# Mikrolysreklamen.net
KiCad netlist of a schematic drawn in Altium Designer
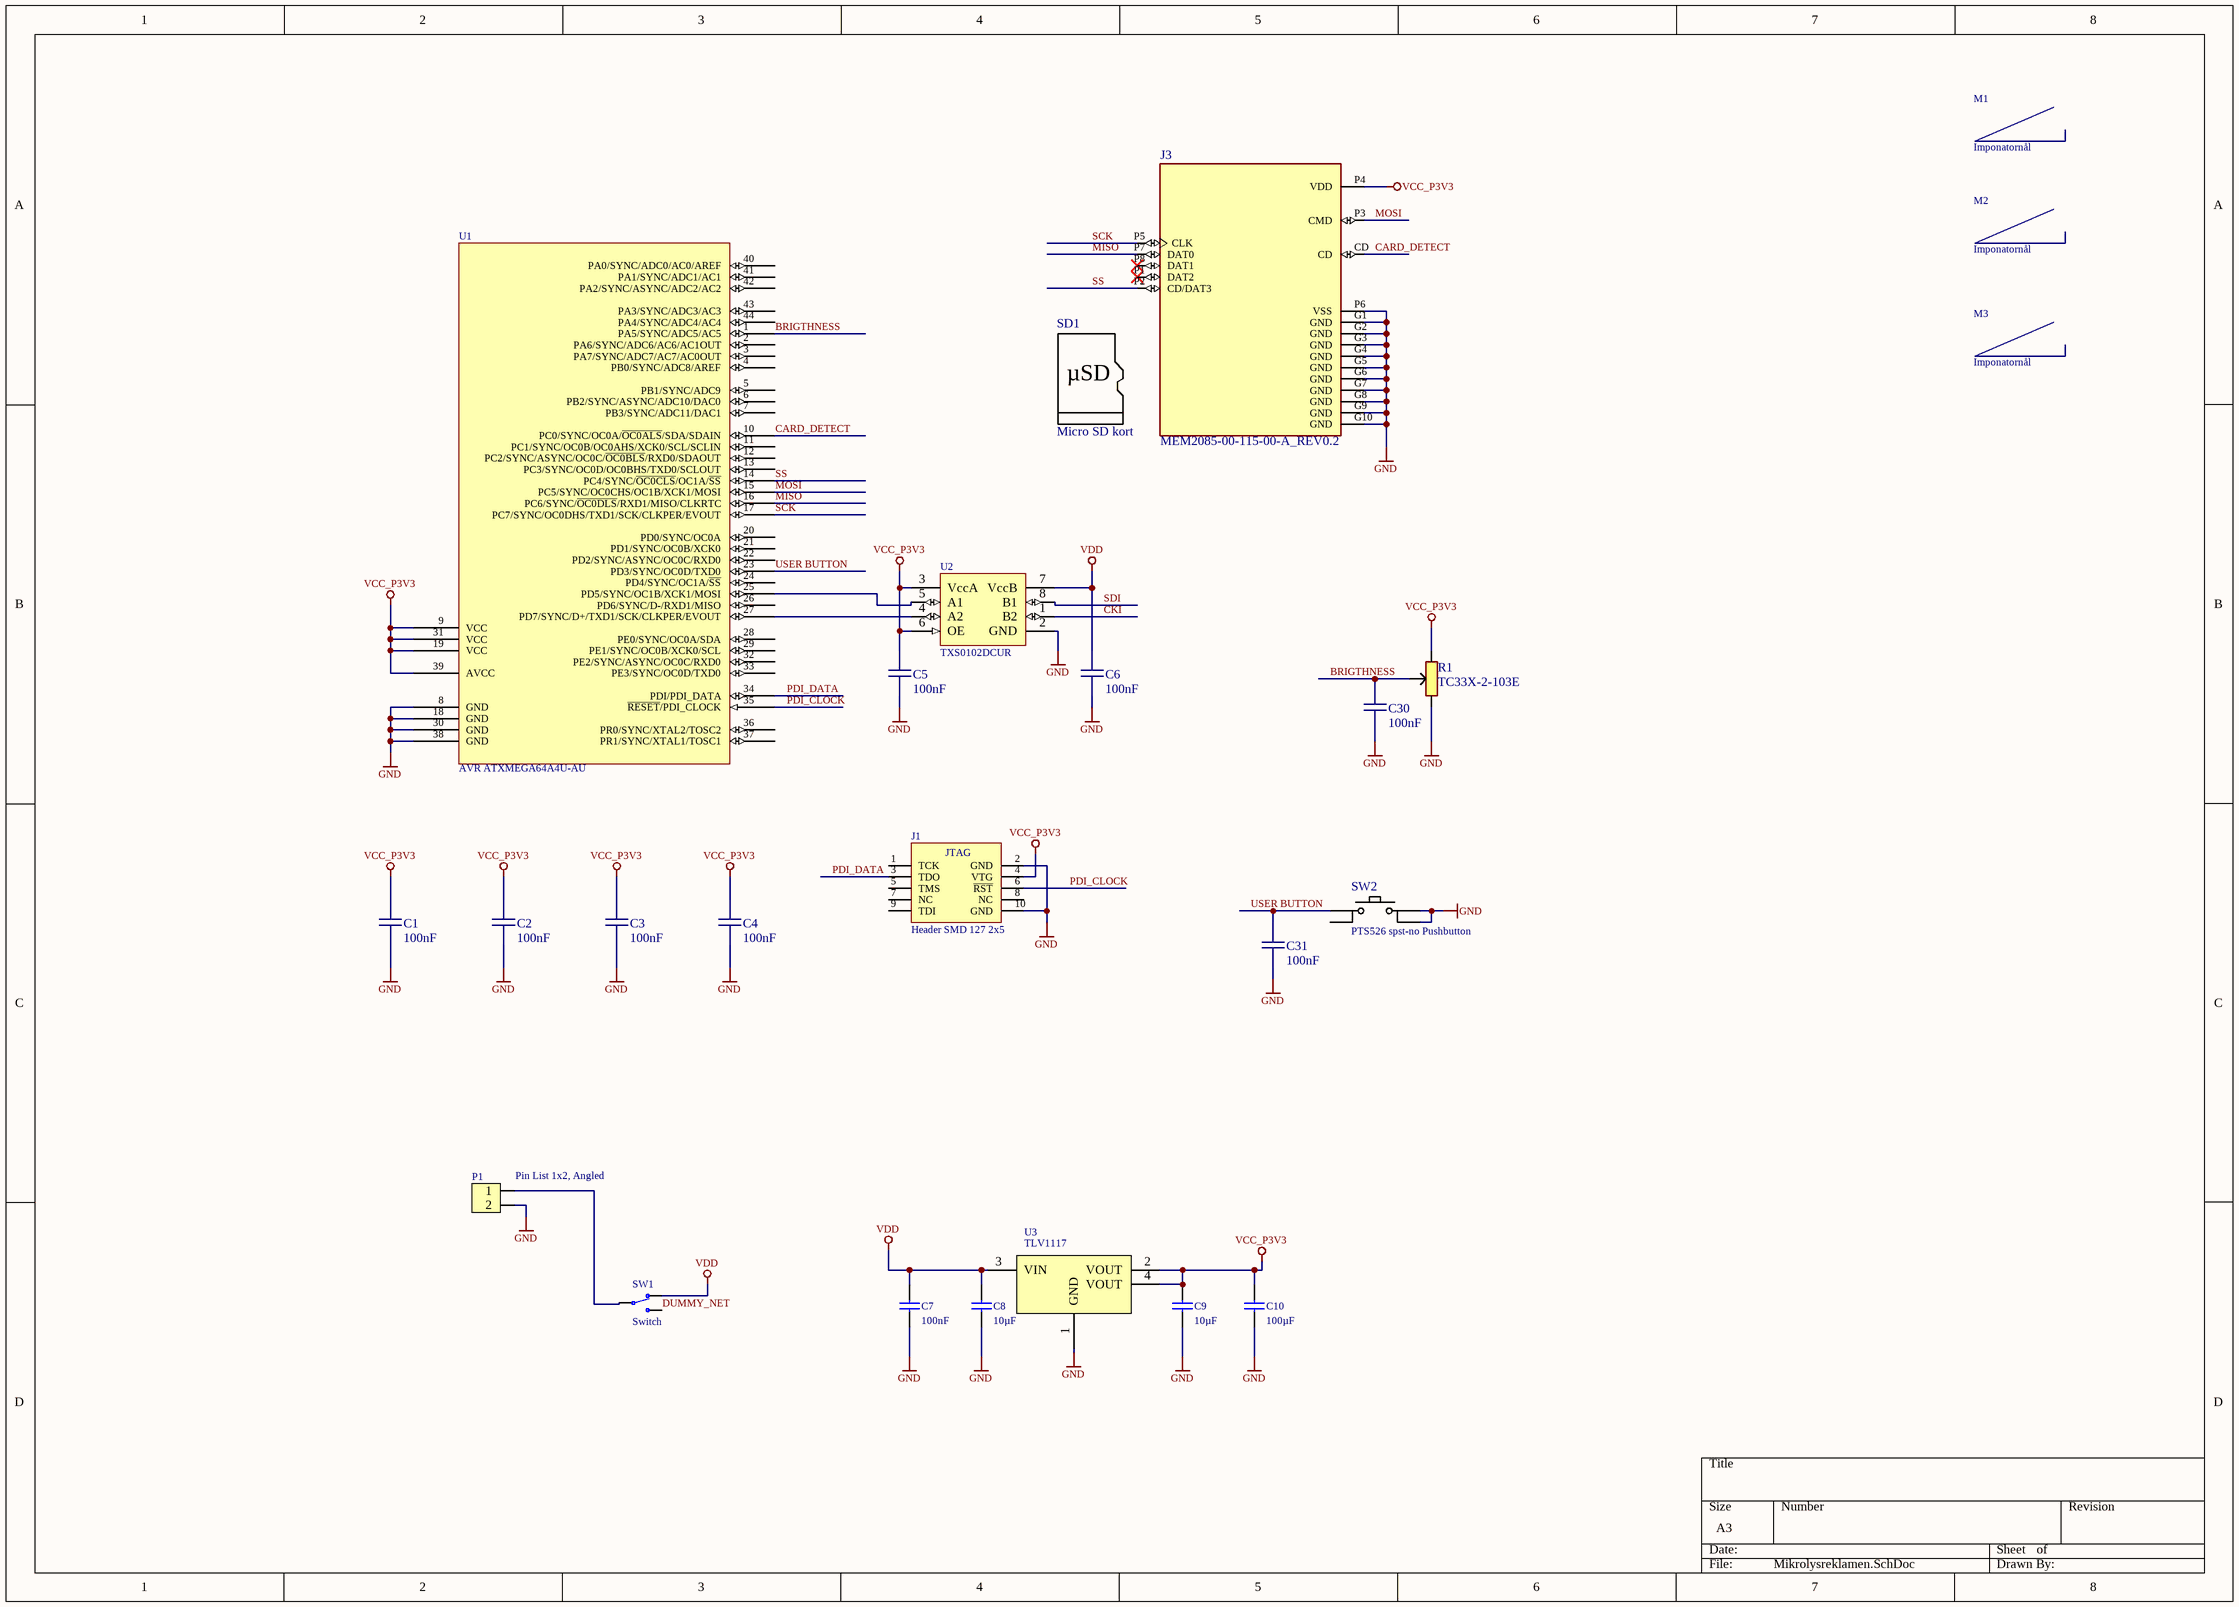
[diagram p0: Mikrolysreklamen.SchDoc]

(export (version "E")
  (design (tool "Eeschema 10.0.6"))
  (components
    (comp (ref "C1")
      (value "100nF")
      (footprint "CAPC0603(1608)55_N")
      (libsource (lib "OVLib_64") (part "CAP"))
    )
    (comp (ref "C2")
      (value "100nF")
      (footprint "CAPC0603(1608)55_N")
      (libsource (lib "OVLib_64") (part "CAP"))
    )
    (comp (ref "C3")
      (value "100nF")
      (footprint "CAPC0603(1608)55_N")
      (libsource (lib "OVLib_64") (part "CAP"))
    )
    (comp (ref "C4")
      (value "100nF")
      (footprint "CAPC0603(1608)55_N")
      (libsource (lib "OVLib_64") (part "CAP"))
    )
    (comp (ref "C5")
      (value "100nF")
      (footprint "CAPC0603(1608)55_N")
      (libsource (lib "OVLib_64") (part "CAP"))
    )
    (comp (ref "C6")
      (value "100nF")
      (footprint "CAPC0603(1608)55_N")
      (libsource (lib "OVLib_64") (part "CAP"))
    )
    (comp (ref "C7")
      (value "100nF")
      (footprint "CAPC1005X04L")
      (description "Capacitor, X7R, ±10%")
      (fields (field (name "PART NUMBER") "C0402-100n") (field (name "PUBLISHER") "Nordic Semiconductor"))
      (libsource (lib "Nordic Passive DB") (part "CAP"))
    )
    (comp (ref "C8")
      (value "10µF")
      (footprint "CAPC1608X06L")
      (description "Capacitor, X5R, ±20%")
      (fields (field (name "PART NUMBER") "C0603-10µ") (field (name "PUBLISHER") "Nordic Semiconductor"))
      (libsource (lib "Nordic Passive DB") (part "CAP"))
    )
    (comp (ref "C9")
      (value "10µF")
      (footprint "CAPC1608X06L")
      (description "Capacitor, X5R, ±20%")
      (fields (field (name "PART NUMBER") "C0603-10µ") (field (name "PUBLISHER") "Nordic Semiconductor"))
      (libsource (lib "Nordic Passive DB") (part "CAP"))
    )
    (comp (ref "C10")
      (value "100µF")
      (footprint "CAPC2012X11L")
      (description "Chip Cap 0805")
      (fields (field (name "PART NUMBER") "C0805-TBD") (field (name "PUBLISHER") "Nordic Semiconductor"))
      (libsource (lib "Nordic Passive DB") (part "CAP"))
    )
    (comp (ref "C30")
      (value "100nF")
      (footprint "CAPC0603(1608)55_N")
      (libsource (lib "OVLib_64") (part "CAP"))
    )
    (comp (ref "C31")
      (value "100nF")
      (footprint "CAPC0603(1608)55_N")
      (libsource (lib "OVLib_64") (part "CAP"))
    )
    (comp (ref "J1")
      (value "Header SMD 127 2x5")
      (footprint "SMDHDRV10P127_2X5_615X330X560B")
      (description "1,27mm Pitch SMD Header")
      (libsource (lib "OVLib") (part "AVRJTAG"))
    )
    (comp (ref "J3")
      (value "MEM2085-00-115-00-A_REV0.2")
      (footprint "GCT_MEM2085-00-115-00-A_REV0.2")
      (description "MicroSD Push pull Memory Card Connector")
      (fields (field (name "MP") "MEM2085-00-115-00-A") (field (name "MF") "Global Connector Technology"))
      (libsource (lib "OVLib_64") (part "MEM2085-00-115-00-A_REV0.2"))
    )
    (comp (ref "M1")
      (value "Imponatornål")
      (footprint "Imponatornaal_liten")
      (description "nål til imponatorplate 20mm (Brooch back)")
      (libsource (lib "OVLib_64") (part "Imponatornaal"))
    )
    (comp (ref "M2")
      (value "Imponatornål")
      (footprint "Imponatornaal_liten")
      (description "nål til imponatorplate 20mm (Brooch back)")
      (libsource (lib "OVLib_64") (part "Imponatornaal"))
    )
    (comp (ref "M3")
      (value "Imponatornål")
      (footprint "Imponatornaal_liten")
      (description "nål til imponatorplate 20mm (Brooch back)")
      (libsource (lib "OVLib_64") (part "Imponatornaal"))
    )
    (comp (ref "P1")
      (value "Pin List 1x2, Angled")
      (footprint "LIST_ANG_1x2-SMD-2.54MM")
      (description "Pin List 1x2, 2.54mm (100mil), Right Angled, SMD")
      (fields
        (field (name "PART NUMBER") "Pin List Ang 1x2 SMD, 2.54mm")
        (field (name "MANUFACTURER") "W-CON")
        (field (name "PUBLISHER") "Nordic Semiconductor")
      )
      (libsource (lib "Nordic Passive DB") (part "CONN-2"))
    )
    (comp (ref "R1")
      (value "TC33X-2-103E")
      (footprint "TRIM_TC33X-2-103E")
      (libsource (lib "OVLib_64") (part "Potmeter"))
    )
    (comp (ref "SD1")
      (value "Micro SD kort")
      (footprint "microsdcard")
      (libsource (lib "OVLib_64") (part "microsdcard"))
    )
    (comp (ref "SW1")
      (value "Switch")
      (footprint "JS102011SAQN")
      (description "SMD slide Switch (ON-ON)")
      (fields
        (field (name "PART NUMBER") "JS102011SAQN")
        (field (name "MANUFACTURER") "C&K Components")
        (field (name "PUBLISHER") "Nordic Semiconductor")
      )
      (libsource (lib "Nordic Discrete DB") (part "SW-SPDT"))
    )
    (comp (ref "SW2")
      (value "PTS526 spst-no Pushbutton")
      (footprint "PTS526_SK15_SMTR2_LFS")
      (libsource (lib "OVLib_64") (part "Pushbutton"))
    )
    (comp (ref "U1")
      (value "AVR ATXMEGA64A4U-AU")
      (footprint "TQFP80P1200X1200X120-44N")
      (description "Mikrokontroller")
      (libsource (lib "OVLib") (part "ATXMEGA-A4U"))
    )
    (comp (ref "U2")
      (value "TXS0102DCUR")
      (footprint "TSSOP50P310X90-8N")
      (description "IC VOLT-LEVEL TRANSLATOR 8-US8")
      (fields
        (field (name "MANUFACTURER") "Texas Instruments")
        (field (name "PUBLISHER") "Nordic Semiconductor")
      )
      (libsource (lib "Nordic Active DB") (part "TXS0102DC"))
    )
    (comp (ref "U3")
      (value "TLV1117")
      (footprint "SOT230P700X180-4N")
      (description "REG LDO 3.3V 0.8A SOT223")
      (fields
        (field (name "PART NUMBER") "TLV1117-33CDCYR")
        (field (name "MANUFACTURER") "Texas Instruments")
        (field (name "PUBLISHER") "Nordic Semiconductor")
      )
      (libsource (lib "Nordic Active DB") (part "LD1117_fixed"))
    )
  )
  (nets
    (net (code "1") (name "/BRIGTHNESS") (class "Default")
      (node (ref "C30") (pin "2") (pinfunction "2_2") (pintype "passive"))
      (node (ref "R1") (pin "2") (pinfunction "2_2") (pintype "passive"))
      (node (ref "U1") (pin "1") (pinfunction "PA5/SYNC/ADC5/AC5_1") (pintype "bidirectional"))
    )
    (net (code "2") (name "/CARD_DETECT") (class "Default")
      (node (ref "J3") (pin "CD") (pinfunction "CD_CD") (pintype "bidirectional"))
      (node (ref "U1") (pin "10") (pinfunction "PC0/SYNC/OC0A/~{OC0ALS}/SDA/SDAIN_10") (pintype "bidirectional"))
    )
    (net (code "3") (name "/CKI") (class "Default")
      (node (ref "U2") (pin "1") (pinfunction "B2_1") (pintype "bidirectional"))
    )
    (net (code "4") (name "/DUMMY_NET") (class "Default")
      (node (ref "SW1") (pin "3") (pinfunction "N.O_3") (pintype "passive"))
    )
    (net (code "5") (name "/MISO") (class "Default")
      (node (ref "J3") (pin "P7") (pinfunction "DAT0_P7") (pintype "bidirectional"))
      (node (ref "U1") (pin "16") (pinfunction "PC6/SYNC/~{OC0DLS}/RXD1/MISO/CLKRTC_16") (pintype "bidirectional"))
    )
    (net (code "6") (name "/MOSI") (class "Default")
      (node (ref "J3") (pin "P3") (pinfunction "CMD_P3") (pintype "bidirectional"))
      (node (ref "U1") (pin "15") (pinfunction "PC5/SYNC/OC0CHS/OC1B/XCK1/MOSI_15") (pintype "bidirectional"))
    )
    (net (code "7") (name "/PDI_CLOCK") (class "Default")
      (node (ref "J1") (pin "6") (pinfunction "~{RST}_6") (pintype "passive"))
      (node (ref "U1") (pin "35") (pinfunction "~{RESET}/PDI_CLOCK_35") (pintype "input"))
    )
    (net (code "8") (name "/PDI_DATA") (class "Default")
      (node (ref "J1") (pin "3") (pinfunction "TDO_3") (pintype "passive"))
      (node (ref "U1") (pin "34") (pinfunction "PDI/PDI_DATA_34") (pintype "bidirectional"))
    )
    (net (code "9") (name "/SCK") (class "Default")
      (node (ref "J3") (pin "P5") (pinfunction "CLK_P5") (pintype "bidirectional"))
      (node (ref "U1") (pin "17") (pinfunction "PC7/SYNC/OC0DHS/TXD1/SCK/CLKPER/EVOUT_17") (pintype "bidirectional"))
    )
    (net (code "10") (name "/SDI") (class "Default")
      (node (ref "U2") (pin "8") (pinfunction "B1_8") (pintype "bidirectional"))
    )
    (net (code "11") (name "/SS") (class "Default")
      (node (ref "J3") (pin "P2") (pinfunction "CD/DAT3_P2") (pintype "bidirectional"))
      (node (ref "U1") (pin "14") (pinfunction "PC4/SYNC/~{OC0CLS}/OC1A/~{SS}_14") (pintype "bidirectional"))
    )
    (net (code "12") (name "/USER BUTTON") (class "Default")
      (node (ref "C31") (pin "2") (pinfunction "2_2") (pintype "passive"))
      (node (ref "SW2") (pin "1") (pinfunction "1_1") (pintype "passive"))
      (node (ref "U1") (pin "23") (pinfunction "PD3/SYNC/OC0D/TXD0_23") (pintype "bidirectional"))
    )
    (net (code "13") (name "GND") (class "Default")
      (node (ref "C1") (pin "1") (pinfunction "1_1") (pintype "passive"))
      (node (ref "C10") (pin "1") (pinfunction "1_1") (pintype "passive"))
      (node (ref "C2") (pin "1") (pinfunction "1_1") (pintype "passive"))
      (node (ref "C3") (pin "1") (pinfunction "1_1") (pintype "passive"))
      (node (ref "C30") (pin "1") (pinfunction "1_1") (pintype "passive"))
      (node (ref "C31") (pin "1") (pinfunction "1_1") (pintype "passive"))
      (node (ref "C4") (pin "1") (pinfunction "1_1") (pintype "passive"))
      (node (ref "C5") (pin "1") (pinfunction "1_1") (pintype "passive"))
      (node (ref "C6") (pin "1") (pinfunction "1_1") (pintype "passive"))
      (node (ref "C7") (pin "1") (pinfunction "1_1") (pintype "passive"))
      (node (ref "C8") (pin "1") (pinfunction "1_1") (pintype "passive"))
      (node (ref "C9") (pin "1") (pinfunction "1_1") (pintype "passive"))
      (node (ref "J1") (pin "10") (pinfunction "GND_10") (pintype "passive"))
      (node (ref "J1") (pin "2") (pinfunction "GND_2") (pintype "passive"))
      (node (ref "J3") (pin "G1") (pinfunction "GND_G1") (pintype "power_in"))
      (node (ref "J3") (pin "G10") (pinfunction "GND_G10") (pintype "power_in"))
      (node (ref "J3") (pin "G2") (pinfunction "GND_G2") (pintype "power_in"))
      (node (ref "J3") (pin "G3") (pinfunction "GND_G3") (pintype "power_in"))
      (node (ref "J3") (pin "G4") (pinfunction "GND_G4") (pintype "power_in"))
      (node (ref "J3") (pin "G5") (pinfunction "GND_G5") (pintype "power_in"))
      (node (ref "J3") (pin "G6") (pinfunction "GND_G6") (pintype "power_in"))
      (node (ref "J3") (pin "G7") (pinfunction "GND_G7") (pintype "power_in"))
      (node (ref "J3") (pin "G8") (pinfunction "GND_G8") (pintype "power_in"))
      (node (ref "J3") (pin "G9") (pinfunction "GND_G9") (pintype "power_in"))
      (node (ref "J3") (pin "P6") (pinfunction "VSS_P6") (pintype "power_in"))
      (node (ref "P1") (pin "2") (pinfunction "2_2") (pintype "passive"))
      (node (ref "R1") (pin "1") (pinfunction "1_1") (pintype "passive"))
      (node (ref "SW2") (pin "3") (pinfunction "3_3") (pintype "passive"))
      (node (ref "SW2") (pin "4") (pinfunction "4_4") (pintype "passive"))
      (node (ref "U1") (pin "18") (pinfunction "GND_18") (pintype "power_in"))
      (node (ref "U1") (pin "30") (pinfunction "GND_30") (pintype "power_in"))
      (node (ref "U1") (pin "38") (pinfunction "GND_38") (pintype "power_in"))
      (node (ref "U1") (pin "8") (pinfunction "GND_8") (pintype "power_in"))
      (node (ref "U2") (pin "2") (pinfunction "GND_2") (pintype "power_in"))
      (node (ref "U3") (pin "1") (pinfunction "GND_1") (pintype "power_in"))
    )
    (net (code "14") (name "Net-(SW1-COM)") (class "Default")
      (node (ref "P1") (pin "1") (pinfunction "1_1") (pintype "passive"))
      (node (ref "SW1") (pin "2") (pinfunction "COM_2") (pintype "passive"))
    )
    (net (code "15") (name "Net-(U1-PD5{slash}SYNC{slash}OC1B{slash}XCK1{slash}MOSI)") (class "Default")
      (node (ref "U1") (pin "25") (pinfunction "PD5/SYNC/OC1B/XCK1/MOSI_25") (pintype "bidirectional"))
      (node (ref "U2") (pin "5") (pinfunction "A1_5") (pintype "bidirectional"))
    )
    (net (code "16") (name "Net-(U1-PD7{slash}SYNC{slash}D+{slash}TXD1{slash}SCK{slash}CLKPER{slash}EVOUT)") (class "Default")
      (node (ref "U1") (pin "27") (pinfunction "PD7/SYNC/D+/TXD1/SCK/CLKPER/EVOUT_27") (pintype "bidirectional"))
      (node (ref "U2") (pin "4") (pinfunction "A2_4") (pintype "bidirectional"))
    )
    (net (code "17") (name "VCC_P3V3") (class "Default")
      (node (ref "C1") (pin "2") (pinfunction "2_2") (pintype "passive"))
      (node (ref "C10") (pin "2") (pinfunction "2_2") (pintype "passive"))
      (node (ref "C2") (pin "2") (pinfunction "2_2") (pintype "passive"))
      (node (ref "C3") (pin "2") (pinfunction "2_2") (pintype "passive"))
      (node (ref "C4") (pin "2") (pinfunction "2_2") (pintype "passive"))
      (node (ref "C5") (pin "2") (pinfunction "2_2") (pintype "passive"))
      (node (ref "C9") (pin "2") (pinfunction "2_2") (pintype "passive"))
      (node (ref "J1") (pin "4") (pinfunction "VTG_4") (pintype "passive"))
      (node (ref "J3") (pin "P4") (pinfunction "VDD_P4") (pintype "power_in"))
      (node (ref "R1") (pin "3") (pinfunction "3_3") (pintype "passive"))
      (node (ref "U1") (pin "19") (pinfunction "VCC_19") (pintype "power_in"))
      (node (ref "U1") (pin "31") (pinfunction "VCC_31") (pintype "power_in"))
      (node (ref "U1") (pin "39") (pinfunction "AVCC_39") (pintype "power_in"))
      (node (ref "U1") (pin "9") (pinfunction "VCC_9") (pintype "power_in"))
      (node (ref "U2") (pin "3") (pinfunction "VccA_3") (pintype "power_in"))
      (node (ref "U2") (pin "6") (pinfunction "OE_6") (pintype "input"))
      (node (ref "U3") (pin "2") (pinfunction "VOUT_2") (pintype "power_in"))
      (node (ref "U3") (pin "4") (pinfunction "VOUT_4") (pintype "power_in"))
    )
    (net (code "18") (name "VDD") (class "Default")
      (node (ref "C6") (pin "2") (pinfunction "2_2") (pintype "passive"))
      (node (ref "C7") (pin "2") (pinfunction "2_2") (pintype "passive"))
      (node (ref "C8") (pin "2") (pinfunction "2_2") (pintype "passive"))
      (node (ref "SW1") (pin "1") (pinfunction "N.C_1") (pintype "passive"))
      (node (ref "U2") (pin "7") (pinfunction "VccB_7") (pintype "power_in"))
      (node (ref "U3") (pin "3") (pinfunction "VIN_3") (pintype "power_in"))
    )
    (net (code "19") (name "unconnected-(J1-NC-Pad7)") (class "Default")
      (node (ref "J1") (pin "7") (pinfunction "NC_7") (pintype "passive"))
    )
    (net (code "20") (name "unconnected-(J1-NC-Pad8)") (class "Default")
      (node (ref "J1") (pin "8") (pinfunction "NC_8") (pintype "passive"))
    )
    (net (code "21") (name "unconnected-(J1-TCK-Pad1)") (class "Default")
      (node (ref "J1") (pin "1") (pinfunction "TCK_1") (pintype "passive"))
    )
    (net (code "22") (name "unconnected-(J1-TDI-Pad9)") (class "Default")
      (node (ref "J1") (pin "9") (pinfunction "TDI_9") (pintype "passive"))
    )
    (net (code "23") (name "unconnected-(J1-TMS-Pad5)") (class "Default")
      (node (ref "J1") (pin "5") (pinfunction "TMS_5") (pintype "passive"))
    )
    (net (code "24") (name "unconnected-(J3-DAT1-PadP8)") (class "Default")
      (node (ref "J3") (pin "P8") (pinfunction "DAT1_P8") (pintype "bidirectional+no_connect"))
    )
    (net (code "25") (name "unconnected-(J3-DAT2-PadP1)") (class "Default")
      (node (ref "J3") (pin "P1") (pinfunction "DAT2_P1") (pintype "bidirectional+no_connect"))
    )
    (net (code "26") (name "unconnected-(SW2-Pad2)") (class "Default")
      (node (ref "SW2") (pin "2") (pinfunction "2_2") (pintype "passive"))
    )
    (net (code "27") (name "unconnected-(U1-PA0{slash}SYNC{slash}ADC0{slash}AC0{slash}AREF-Pad40)") (class "Default")
      (node (ref "U1") (pin "40") (pinfunction "PA0/SYNC/ADC0/AC0/AREF_40") (pintype "bidirectional"))
    )
    (net (code "28") (name "unconnected-(U1-PA1{slash}SYNC{slash}ADC1{slash}AC1-Pad41)") (class "Default")
      (node (ref "U1") (pin "41") (pinfunction "PA1/SYNC/ADC1/AC1_41") (pintype "bidirectional"))
    )
    (net (code "29") (name "unconnected-(U1-PA2{slash}SYNC{slash}ASYNC{slash}ADC2{slash}AC2-Pad42)") (class "Default")
      (node (ref "U1") (pin "42") (pinfunction "PA2/SYNC/ASYNC/ADC2/AC2_42") (pintype "bidirectional"))
    )
    (net (code "30") (name "unconnected-(U1-PA3{slash}SYNC{slash}ADC3{slash}AC3-Pad43)") (class "Default")
      (node (ref "U1") (pin "43") (pinfunction "PA3/SYNC/ADC3/AC3_43") (pintype "bidirectional"))
    )
    (net (code "31") (name "unconnected-(U1-PA4{slash}SYNC{slash}ADC4{slash}AC4-Pad44)") (class "Default")
      (node (ref "U1") (pin "44") (pinfunction "PA4/SYNC/ADC4/AC4_44") (pintype "bidirectional"))
    )
    (net (code "32") (name "unconnected-(U1-PA6{slash}SYNC{slash}ADC6{slash}AC6{slash}AC1OUT-Pad2)") (class "Default")
      (node (ref "U1") (pin "2") (pinfunction "PA6/SYNC/ADC6/AC6/AC1OUT_2") (pintype "bidirectional"))
    )
    (net (code "33") (name "unconnected-(U1-PA7{slash}SYNC{slash}ADC7{slash}AC7{slash}AC0OUT-Pad3)") (class "Default")
      (node (ref "U1") (pin "3") (pinfunction "PA7/SYNC/ADC7/AC7/AC0OUT_3") (pintype "bidirectional"))
    )
    (net (code "34") (name "unconnected-(U1-PB0{slash}SYNC{slash}ADC8{slash}AREF-Pad4)") (class "Default")
      (node (ref "U1") (pin "4") (pinfunction "PB0/SYNC/ADC8/AREF_4") (pintype "bidirectional"))
    )
    (net (code "35") (name "unconnected-(U1-PB1{slash}SYNC{slash}ADC9-Pad5)") (class "Default")
      (node (ref "U1") (pin "5") (pinfunction "PB1/SYNC/ADC9_5") (pintype "bidirectional"))
    )
    (net (code "36") (name "unconnected-(U1-PB2{slash}SYNC{slash}ASYNC{slash}ADC10{slash}DAC0-Pad6)") (class "Default")
      (node (ref "U1") (pin "6") (pinfunction "PB2/SYNC/ASYNC/ADC10/DAC0_6") (pintype "bidirectional"))
    )
    (net (code "37") (name "unconnected-(U1-PB3{slash}SYNC{slash}ADC11{slash}DAC1-Pad7)") (class "Default")
      (node (ref "U1") (pin "7") (pinfunction "PB3/SYNC/ADC11/DAC1_7") (pintype "bidirectional"))
    )
    (net (code "38") (name "unconnected-(U1-PC1{slash}SYNC{slash}OC0B{slash}OC0AHS{slash}XCK0{slash}SCL{slash}SCLIN-Pad11)") (class "Default")
      (node (ref "U1") (pin "11") (pinfunction "PC1/SYNC/OC0B/OC0AHS/XCK0/SCL/SCLIN_11") (pintype "bidirectional"))
    )
    (net (code "39") (name "unconnected-(U1-PC2{slash}SYNC{slash}ASYNC{slash}OC0C{slash}~{OC0BLS}{slash}RXD0{slash}SDAOUT-Pad12)") (class "Default")
      (node (ref "U1") (pin "12") (pinfunction "PC2/SYNC/ASYNC/OC0C/~{OC0BLS}/RXD0/SDAOUT_12") (pintype "bidirectional"))
    )
    (net (code "40") (name "unconnected-(U1-PC3{slash}SYNC{slash}OC0D{slash}OC0BHS{slash}TXD0{slash}SCLOUT-Pad13)") (class "Default")
      (node (ref "U1") (pin "13") (pinfunction "PC3/SYNC/OC0D/OC0BHS/TXD0/SCLOUT_13") (pintype "bidirectional"))
    )
    (net (code "41") (name "unconnected-(U1-PD0{slash}SYNC{slash}OC0A-Pad20)") (class "Default")
      (node (ref "U1") (pin "20") (pinfunction "PD0/SYNC/OC0A_20") (pintype "bidirectional"))
    )
    (net (code "42") (name "unconnected-(U1-PD1{slash}SYNC{slash}OC0B{slash}XCK0-Pad21)") (class "Default")
      (node (ref "U1") (pin "21") (pinfunction "PD1/SYNC/OC0B/XCK0_21") (pintype "bidirectional"))
    )
    (net (code "43") (name "unconnected-(U1-PD2{slash}SYNC{slash}ASYNC{slash}OC0C{slash}RXD0-Pad22)") (class "Default")
      (node (ref "U1") (pin "22") (pinfunction "PD2/SYNC/ASYNC/OC0C/RXD0_22") (pintype "bidirectional"))
    )
    (net (code "44") (name "unconnected-(U1-PD4{slash}SYNC{slash}OC1A{slash}~{SS}-Pad24)") (class "Default")
      (node (ref "U1") (pin "24") (pinfunction "PD4/SYNC/OC1A/~{SS}_24") (pintype "bidirectional"))
    )
    (net (code "45") (name "unconnected-(U1-PD6{slash}SYNC{slash}D-{slash}RXD1{slash}MISO-Pad26)") (class "Default")
      (node (ref "U1") (pin "26") (pinfunction "PD6/SYNC/D-/RXD1/MISO_26") (pintype "bidirectional"))
    )
    (net (code "46") (name "unconnected-(U1-PE0{slash}SYNC{slash}OC0A{slash}SDA-Pad28)") (class "Default")
      (node (ref "U1") (pin "28") (pinfunction "PE0/SYNC/OC0A/SDA_28") (pintype "bidirectional"))
    )
    (net (code "47") (name "unconnected-(U1-PE1{slash}SYNC{slash}OC0B{slash}XCK0{slash}SCL-Pad29)") (class "Default")
      (node (ref "U1") (pin "29") (pinfunction "PE1/SYNC/OC0B/XCK0/SCL_29") (pintype "bidirectional"))
    )
    (net (code "48") (name "unconnected-(U1-PE2{slash}SYNC{slash}ASYNC{slash}OC0C{slash}RXD0-Pad32)") (class "Default")
      (node (ref "U1") (pin "32") (pinfunction "PE2/SYNC/ASYNC/OC0C/RXD0_32") (pintype "bidirectional"))
    )
    (net (code "49") (name "unconnected-(U1-PE3{slash}SYNC{slash}OC0D{slash}TXD0-Pad33)") (class "Default")
      (node (ref "U1") (pin "33") (pinfunction "PE3/SYNC/OC0D/TXD0_33") (pintype "bidirectional"))
    )
    (net (code "50") (name "unconnected-(U1-PR0{slash}SYNC{slash}XTAL2{slash}TOSC2-Pad36)") (class "Default")
      (node (ref "U1") (pin "36") (pinfunction "PR0/SYNC/XTAL2/TOSC2_36") (pintype "bidirectional"))
    )
    (net (code "51") (name "unconnected-(U1-PR1{slash}SYNC{slash}XTAL1{slash}TOSC1-Pad37)") (class "Default")
      (node (ref "U1") (pin "37") (pinfunction "PR1/SYNC/XTAL1/TOSC1_37") (pintype "bidirectional"))
    )
  )
)
